# ODU_Display_0603.net
KiCad netlist of a schematic drawn in EAGLE
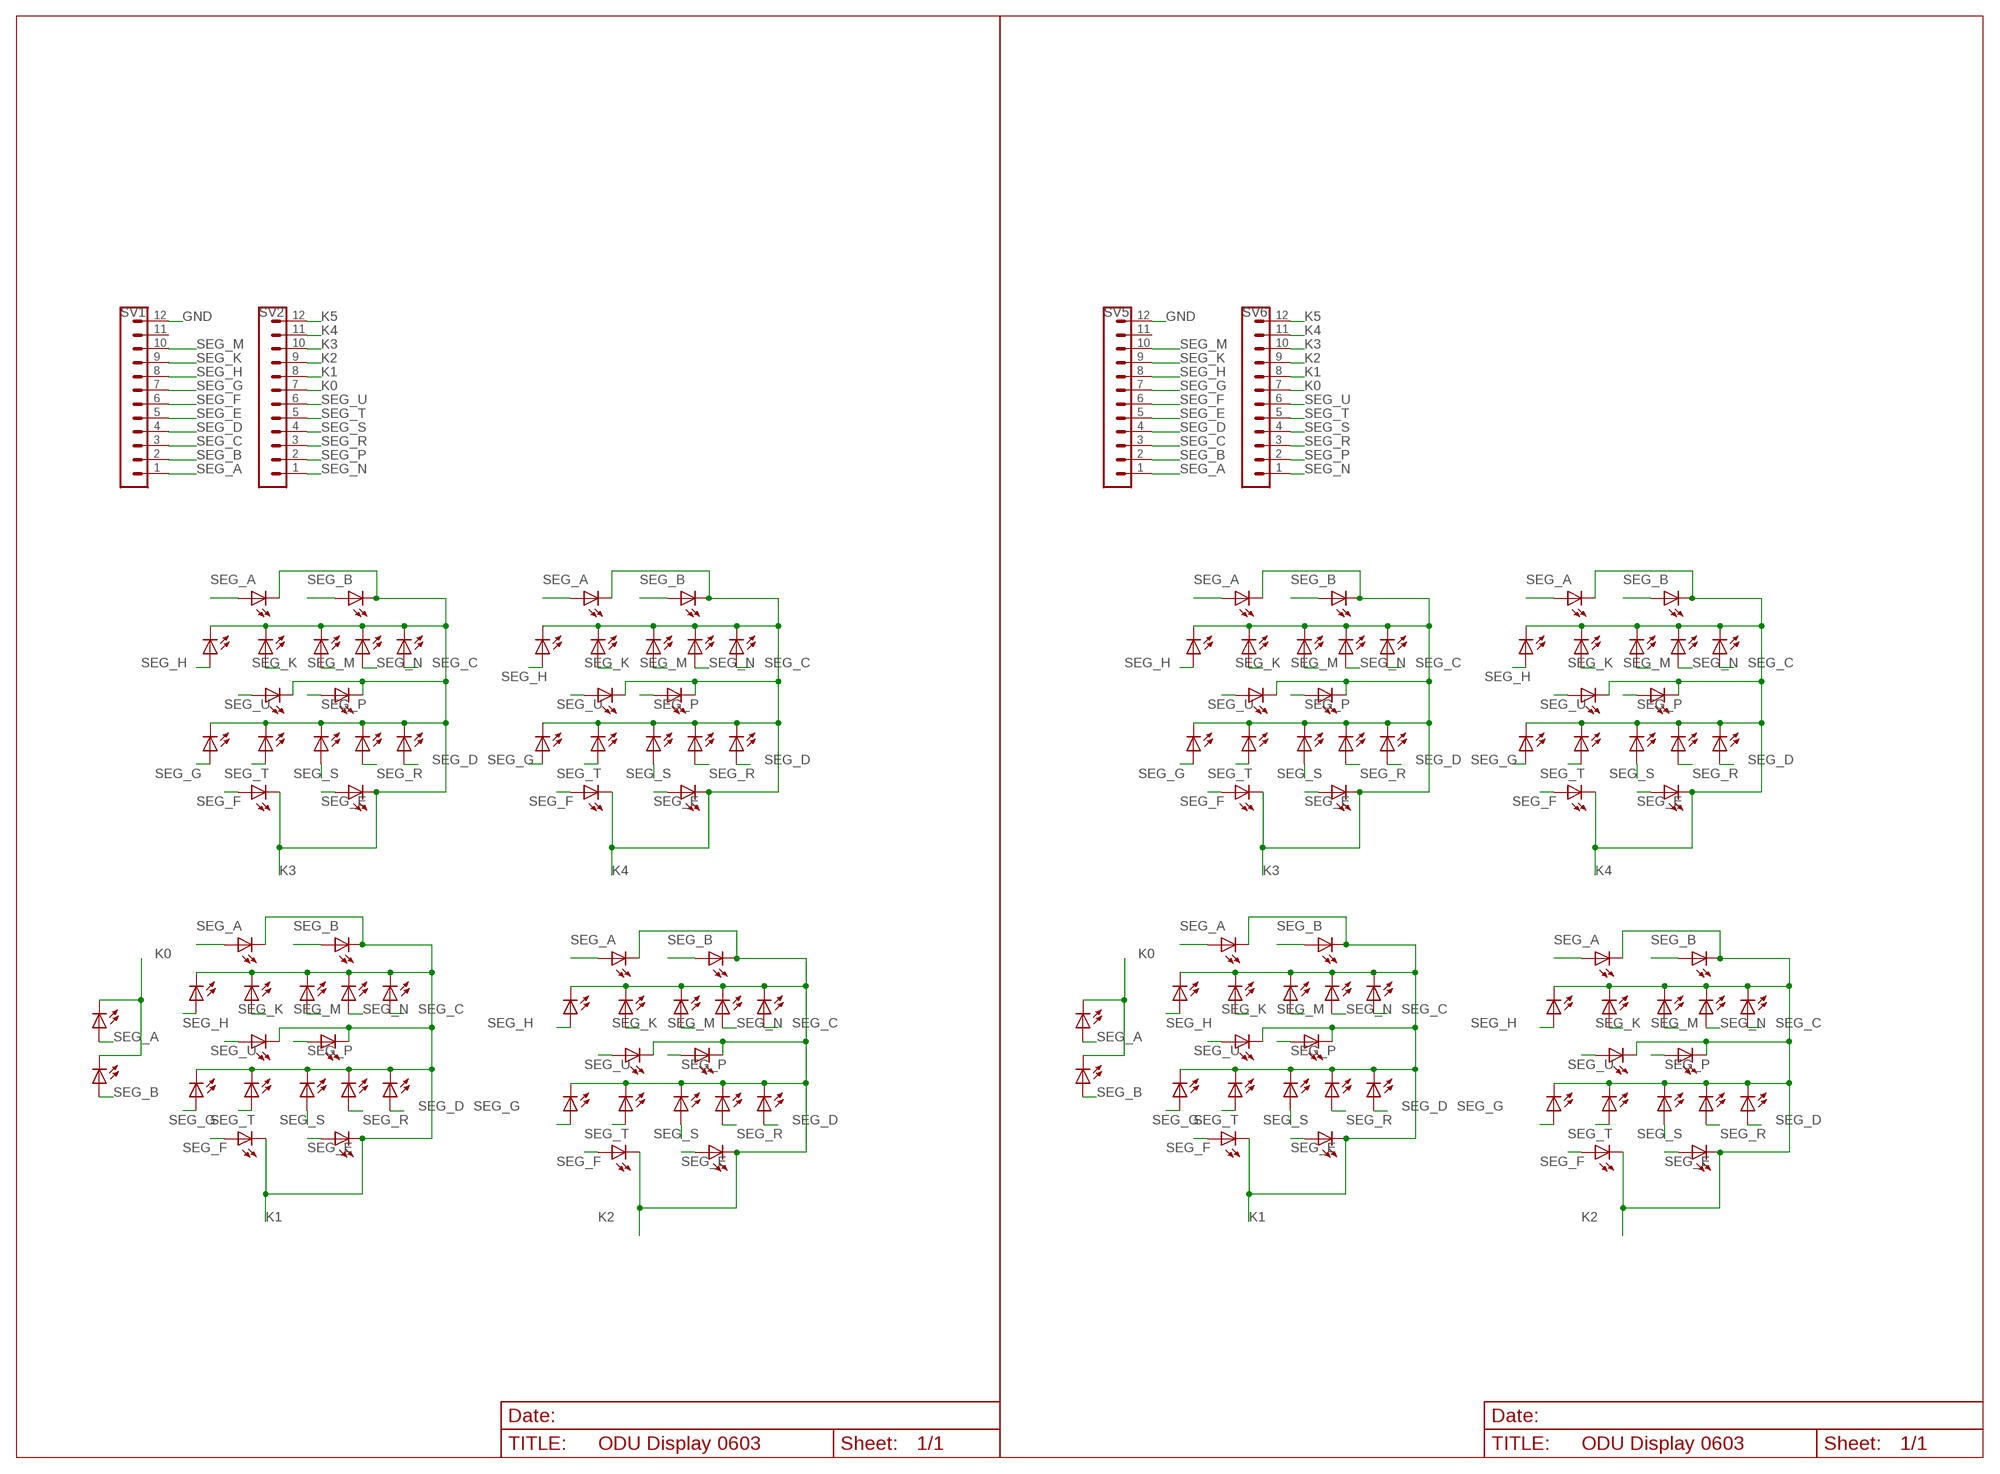
[diagram p0: schematic, sheet 1]

(export (version "E")
  (design (tool "Eeschema 10.0.6"))
  (components
    (comp (ref "LED_A1")
      (value "LEDSMT0603_1")
      (footprint "eagle-import:CHIPLED_0603")
      (libsource (lib "eagle-import") (part "LED0603_1SMT"))
    )
    (comp (ref "LED_A2")
      (value "LEDSMT0603_1")
      (footprint "eagle-import:CHIPLED_0603")
      (libsource (lib "eagle-import") (part "LED0603_1SMT"))
    )
    (comp (ref "LED_A3")
      (value "LEDSMT0603_1")
      (footprint "eagle-import:CHIPLED_0603")
      (libsource (lib "eagle-import") (part "LED0603_1SMT"))
    )
    (comp (ref "LED_A4")
      (value "LEDSMT0603_1")
      (footprint "eagle-import:CHIPLED_0603")
      (libsource (lib "eagle-import") (part "LED0603_1SMT"))
    )
    (comp (ref "LED_A9")
      (value "LEDSMT0603_1")
      (footprint "eagle-import:CHIPLED_0603")
      (libsource (lib "eagle-import") (part "LED0603_1SMT"))
    )
    (comp (ref "LED_A10")
      (value "LEDSMT0603_1")
      (footprint "eagle-import:CHIPLED_0603")
      (libsource (lib "eagle-import") (part "LED0603_1SMT"))
    )
    (comp (ref "LED_A11")
      (value "LEDSMT0603_1")
      (footprint "eagle-import:CHIPLED_0603")
      (libsource (lib "eagle-import") (part "LED0603_1SMT"))
    )
    (comp (ref "LED_A12")
      (value "LEDSMT0603_1")
      (footprint "eagle-import:CHIPLED_0603")
      (libsource (lib "eagle-import") (part "LED0603_1SMT"))
    )
    (comp (ref "LED_B1")
      (value "LEDSMT0603_1")
      (footprint "eagle-import:CHIPLED_0603")
      (libsource (lib "eagle-import") (part "LED0603_1SMT"))
    )
    (comp (ref "LED_B2")
      (value "LEDSMT0603_1")
      (footprint "eagle-import:CHIPLED_0603")
      (libsource (lib "eagle-import") (part "LED0603_1SMT"))
    )
    (comp (ref "LED_B3")
      (value "LEDSMT0603_1")
      (footprint "eagle-import:CHIPLED_0603")
      (libsource (lib "eagle-import") (part "LED0603_1SMT"))
    )
    (comp (ref "LED_B4")
      (value "LEDSMT0603_1")
      (footprint "eagle-import:CHIPLED_0603")
      (libsource (lib "eagle-import") (part "LED0603_1SMT"))
    )
    (comp (ref "LED_B9")
      (value "LEDSMT0603_1")
      (footprint "eagle-import:CHIPLED_0603")
      (libsource (lib "eagle-import") (part "LED0603_1SMT"))
    )
    (comp (ref "LED_B10")
      (value "LEDSMT0603_1")
      (footprint "eagle-import:CHIPLED_0603")
      (libsource (lib "eagle-import") (part "LED0603_1SMT"))
    )
    (comp (ref "LED_B11")
      (value "LEDSMT0603_1")
      (footprint "eagle-import:CHIPLED_0603")
      (libsource (lib "eagle-import") (part "LED0603_1SMT"))
    )
    (comp (ref "LED_B12")
      (value "LEDSMT0603_1")
      (footprint "eagle-import:CHIPLED_0603")
      (libsource (lib "eagle-import") (part "LED0603_1SMT"))
    )
    (comp (ref "LED_C1")
      (value "LEDSMT0603_1")
      (footprint "eagle-import:CHIPLED_0603")
      (libsource (lib "eagle-import") (part "LED0603_1SMT"))
    )
    (comp (ref "LED_C2")
      (value "LEDSMT0603_1")
      (footprint "eagle-import:CHIPLED_0603")
      (libsource (lib "eagle-import") (part "LED0603_1SMT"))
    )
    (comp (ref "LED_C3")
      (value "LEDSMT0603_1")
      (footprint "eagle-import:CHIPLED_0603")
      (libsource (lib "eagle-import") (part "LED0603_1SMT"))
    )
    (comp (ref "LED_C4")
      (value "LEDSMT0603_1")
      (footprint "eagle-import:CHIPLED_0603")
      (libsource (lib "eagle-import") (part "LED0603_1SMT"))
    )
    (comp (ref "LED_C9")
      (value "LEDSMT0603_1")
      (footprint "eagle-import:CHIPLED_0603")
      (libsource (lib "eagle-import") (part "LED0603_1SMT"))
    )
    (comp (ref "LED_C10")
      (value "LEDSMT0603_1")
      (footprint "eagle-import:CHIPLED_0603")
      (libsource (lib "eagle-import") (part "LED0603_1SMT"))
    )
    (comp (ref "LED_C11")
      (value "LEDSMT0603_1")
      (footprint "eagle-import:CHIPLED_0603")
      (libsource (lib "eagle-import") (part "LED0603_1SMT"))
    )
    (comp (ref "LED_C12")
      (value "LEDSMT0603_1")
      (footprint "eagle-import:CHIPLED_0603")
      (libsource (lib "eagle-import") (part "LED0603_1SMT"))
    )
    (comp (ref "LED_D1")
      (value "LEDSMT0603_1")
      (footprint "eagle-import:CHIPLED_0603")
      (libsource (lib "eagle-import") (part "LED0603_1SMT"))
    )
    (comp (ref "LED_D2")
      (value "LEDSMT0603_1")
      (footprint "eagle-import:CHIPLED_0603")
      (libsource (lib "eagle-import") (part "LED0603_1SMT"))
    )
    (comp (ref "LED_D3")
      (value "LEDSMT0603_1")
      (footprint "eagle-import:CHIPLED_0603")
      (libsource (lib "eagle-import") (part "LED0603_1SMT"))
    )
    (comp (ref "LED_D4")
      (value "LEDSMT0603_1")
      (footprint "eagle-import:CHIPLED_0603")
      (libsource (lib "eagle-import") (part "LED0603_1SMT"))
    )
    (comp (ref "LED_D9")
      (value "LEDSMT0603_1")
      (footprint "eagle-import:CHIPLED_0603")
      (libsource (lib "eagle-import") (part "LED0603_1SMT"))
    )
    (comp (ref "LED_D10")
      (value "LEDSMT0603_1")
      (footprint "eagle-import:CHIPLED_0603")
      (libsource (lib "eagle-import") (part "LED0603_1SMT"))
    )
    (comp (ref "LED_D11")
      (value "LEDSMT0603_1")
      (footprint "eagle-import:CHIPLED_0603")
      (libsource (lib "eagle-import") (part "LED0603_1SMT"))
    )
    (comp (ref "LED_D12")
      (value "LEDSMT0603_1")
      (footprint "eagle-import:CHIPLED_0603")
      (libsource (lib "eagle-import") (part "LED0603_1SMT"))
    )
    (comp (ref "LED_E1")
      (value "LEDSMT0603_1")
      (footprint "eagle-import:CHIPLED_0603")
      (libsource (lib "eagle-import") (part "LED0603_1SMT"))
    )
    (comp (ref "LED_E2")
      (value "LEDSMT0603_1")
      (footprint "eagle-import:CHIPLED_0603")
      (libsource (lib "eagle-import") (part "LED0603_1SMT"))
    )
    (comp (ref "LED_E3")
      (value "LEDSMT0603_1")
      (footprint "eagle-import:CHIPLED_0603")
      (libsource (lib "eagle-import") (part "LED0603_1SMT"))
    )
    (comp (ref "LED_E4")
      (value "LEDSMT0603_1")
      (footprint "eagle-import:CHIPLED_0603")
      (libsource (lib "eagle-import") (part "LED0603_1SMT"))
    )
    (comp (ref "LED_E9")
      (value "LEDSMT0603_1")
      (footprint "eagle-import:CHIPLED_0603")
      (libsource (lib "eagle-import") (part "LED0603_1SMT"))
    )
    (comp (ref "LED_E10")
      (value "LEDSMT0603_1")
      (footprint "eagle-import:CHIPLED_0603")
      (libsource (lib "eagle-import") (part "LED0603_1SMT"))
    )
    (comp (ref "LED_E11")
      (value "LEDSMT0603_1")
      (footprint "eagle-import:CHIPLED_0603")
      (libsource (lib "eagle-import") (part "LED0603_1SMT"))
    )
    (comp (ref "LED_E12")
      (value "LEDSMT0603_1")
      (footprint "eagle-import:CHIPLED_0603")
      (libsource (lib "eagle-import") (part "LED0603_1SMT"))
    )
    (comp (ref "LED_F1")
      (value "LEDSMT0603_1")
      (footprint "eagle-import:CHIPLED_0603")
      (libsource (lib "eagle-import") (part "LED0603_1SMT"))
    )
    (comp (ref "LED_F2")
      (value "LEDSMT0603_1")
      (footprint "eagle-import:CHIPLED_0603")
      (libsource (lib "eagle-import") (part "LED0603_1SMT"))
    )
    (comp (ref "LED_F3")
      (value "LEDSMT0603_1")
      (footprint "eagle-import:CHIPLED_0603")
      (libsource (lib "eagle-import") (part "LED0603_1SMT"))
    )
    (comp (ref "LED_F4")
      (value "LEDSMT0603_1")
      (footprint "eagle-import:CHIPLED_0603")
      (libsource (lib "eagle-import") (part "LED0603_1SMT"))
    )
    (comp (ref "LED_F9")
      (value "LEDSMT0603_1")
      (footprint "eagle-import:CHIPLED_0603")
      (libsource (lib "eagle-import") (part "LED0603_1SMT"))
    )
    (comp (ref "LED_F10")
      (value "LEDSMT0603_1")
      (footprint "eagle-import:CHIPLED_0603")
      (libsource (lib "eagle-import") (part "LED0603_1SMT"))
    )
    (comp (ref "LED_F11")
      (value "LEDSMT0603_1")
      (footprint "eagle-import:CHIPLED_0603")
      (libsource (lib "eagle-import") (part "LED0603_1SMT"))
    )
    (comp (ref "LED_F12")
      (value "LEDSMT0603_1")
      (footprint "eagle-import:CHIPLED_0603")
      (libsource (lib "eagle-import") (part "LED0603_1SMT"))
    )
    (comp (ref "LED_G1")
      (value "LEDSMT0603_1")
      (footprint "eagle-import:CHIPLED_0603")
      (libsource (lib "eagle-import") (part "LED0603_1SMT"))
    )
    (comp (ref "LED_G2")
      (value "LEDSMT0603_1")
      (footprint "eagle-import:CHIPLED_0603")
      (libsource (lib "eagle-import") (part "LED0603_1SMT"))
    )
    (comp (ref "LED_G3")
      (value "LEDSMT0603_1")
      (footprint "eagle-import:CHIPLED_0603")
      (libsource (lib "eagle-import") (part "LED0603_1SMT"))
    )
    (comp (ref "LED_G4")
      (value "LEDSMT0603_1")
      (footprint "eagle-import:CHIPLED_0603")
      (libsource (lib "eagle-import") (part "LED0603_1SMT"))
    )
    (comp (ref "LED_G9")
      (value "LEDSMT0603_1")
      (footprint "eagle-import:CHIPLED_0603")
      (libsource (lib "eagle-import") (part "LED0603_1SMT"))
    )
    (comp (ref "LED_G10")
      (value "LEDSMT0603_1")
      (footprint "eagle-import:CHIPLED_0603")
      (libsource (lib "eagle-import") (part "LED0603_1SMT"))
    )
    (comp (ref "LED_G11")
      (value "LEDSMT0603_1")
      (footprint "eagle-import:CHIPLED_0603")
      (libsource (lib "eagle-import") (part "LED0603_1SMT"))
    )
    (comp (ref "LED_G12")
      (value "LEDSMT0603_1")
      (footprint "eagle-import:CHIPLED_0603")
      (libsource (lib "eagle-import") (part "LED0603_1SMT"))
    )
    (comp (ref "LED_H1")
      (value "LEDSMT0603_1")
      (footprint "eagle-import:CHIPLED_0603")
      (libsource (lib "eagle-import") (part "LED0603_1SMT"))
    )
    (comp (ref "LED_H2")
      (value "LEDSMT0603_1")
      (footprint "eagle-import:CHIPLED_0603")
      (libsource (lib "eagle-import") (part "LED0603_1SMT"))
    )
    (comp (ref "LED_H3")
      (value "LEDSMT0603_1")
      (footprint "eagle-import:CHIPLED_0603")
      (libsource (lib "eagle-import") (part "LED0603_1SMT"))
    )
    (comp (ref "LED_H4")
      (value "LEDSMT0603_1")
      (footprint "eagle-import:CHIPLED_0603")
      (libsource (lib "eagle-import") (part "LED0603_1SMT"))
    )
    (comp (ref "LED_H9")
      (value "LEDSMT0603_1")
      (footprint "eagle-import:CHIPLED_0603")
      (libsource (lib "eagle-import") (part "LED0603_1SMT"))
    )
    (comp (ref "LED_H10")
      (value "LEDSMT0603_1")
      (footprint "eagle-import:CHIPLED_0603")
      (libsource (lib "eagle-import") (part "LED0603_1SMT"))
    )
    (comp (ref "LED_H11")
      (value "LEDSMT0603_1")
      (footprint "eagle-import:CHIPLED_0603")
      (libsource (lib "eagle-import") (part "LED0603_1SMT"))
    )
    (comp (ref "LED_H12")
      (value "LEDSMT0603_1")
      (footprint "eagle-import:CHIPLED_0603")
      (libsource (lib "eagle-import") (part "LED0603_1SMT"))
    )
    (comp (ref "LED_K1")
      (value "LEDSMT0603_1")
      (footprint "eagle-import:CHIPLED_0603")
      (libsource (lib "eagle-import") (part "LED0603_1SMT"))
    )
    (comp (ref "LED_K2")
      (value "LEDSMT0603_1")
      (footprint "eagle-import:CHIPLED_0603")
      (libsource (lib "eagle-import") (part "LED0603_1SMT"))
    )
    (comp (ref "LED_K3")
      (value "LEDSMT0603_1")
      (footprint "eagle-import:CHIPLED_0603")
      (libsource (lib "eagle-import") (part "LED0603_1SMT"))
    )
    (comp (ref "LED_K4")
      (value "LEDSMT0603_1")
      (footprint "eagle-import:CHIPLED_0603")
      (libsource (lib "eagle-import") (part "LED0603_1SMT"))
    )
    (comp (ref "LED_K9")
      (value "LEDSMT0603_1")
      (footprint "eagle-import:CHIPLED_0603")
      (libsource (lib "eagle-import") (part "LED0603_1SMT"))
    )
    (comp (ref "LED_K10")
      (value "LEDSMT0603_1")
      (footprint "eagle-import:CHIPLED_0603")
      (libsource (lib "eagle-import") (part "LED0603_1SMT"))
    )
    (comp (ref "LED_K11")
      (value "LEDSMT0603_1")
      (footprint "eagle-import:CHIPLED_0603")
      (libsource (lib "eagle-import") (part "LED0603_1SMT"))
    )
    (comp (ref "LED_K12")
      (value "LEDSMT0603_1")
      (footprint "eagle-import:CHIPLED_0603")
      (libsource (lib "eagle-import") (part "LED0603_1SMT"))
    )
    (comp (ref "LED_M1")
      (value "LEDSMT0603_1")
      (footprint "eagle-import:CHIPLED_0603")
      (libsource (lib "eagle-import") (part "LED0603_1SMT"))
    )
    (comp (ref "LED_M2")
      (value "LEDSMT0603_1")
      (footprint "eagle-import:CHIPLED_0603")
      (libsource (lib "eagle-import") (part "LED0603_1SMT"))
    )
    (comp (ref "LED_M3")
      (value "LEDSMT0603_1")
      (footprint "eagle-import:CHIPLED_0603")
      (libsource (lib "eagle-import") (part "LED0603_1SMT"))
    )
    (comp (ref "LED_M4")
      (value "LEDSMT0603_1")
      (footprint "eagle-import:CHIPLED_0603")
      (libsource (lib "eagle-import") (part "LED0603_1SMT"))
    )
    (comp (ref "LED_M9")
      (value "LEDSMT0603_1")
      (footprint "eagle-import:CHIPLED_0603")
      (libsource (lib "eagle-import") (part "LED0603_1SMT"))
    )
    (comp (ref "LED_M10")
      (value "LEDSMT0603_1")
      (footprint "eagle-import:CHIPLED_0603")
      (libsource (lib "eagle-import") (part "LED0603_1SMT"))
    )
    (comp (ref "LED_M11")
      (value "LEDSMT0603_1")
      (footprint "eagle-import:CHIPLED_0603")
      (libsource (lib "eagle-import") (part "LED0603_1SMT"))
    )
    (comp (ref "LED_M12")
      (value "LEDSMT0603_1")
      (footprint "eagle-import:CHIPLED_0603")
      (libsource (lib "eagle-import") (part "LED0603_1SMT"))
    )
    (comp (ref "LED_N1")
      (value "LEDSMT0603_1")
      (footprint "eagle-import:CHIPLED_0603")
      (libsource (lib "eagle-import") (part "LED0603_1SMT"))
    )
    (comp (ref "LED_N2")
      (value "LEDSMT0603_1")
      (footprint "eagle-import:CHIPLED_0603")
      (libsource (lib "eagle-import") (part "LED0603_1SMT"))
    )
    (comp (ref "LED_N3")
      (value "LEDSMT0603_1")
      (footprint "eagle-import:CHIPLED_0603")
      (libsource (lib "eagle-import") (part "LED0603_1SMT"))
    )
    (comp (ref "LED_N4")
      (value "LEDSMT0603_1")
      (footprint "eagle-import:CHIPLED_0603")
      (libsource (lib "eagle-import") (part "LED0603_1SMT"))
    )
    (comp (ref "LED_N9")
      (value "LEDSMT0603_1")
      (footprint "eagle-import:CHIPLED_0603")
      (libsource (lib "eagle-import") (part "LED0603_1SMT"))
    )
    (comp (ref "LED_N10")
      (value "LEDSMT0603_1")
      (footprint "eagle-import:CHIPLED_0603")
      (libsource (lib "eagle-import") (part "LED0603_1SMT"))
    )
    (comp (ref "LED_N11")
      (value "LEDSMT0603_1")
      (footprint "eagle-import:CHIPLED_0603")
      (libsource (lib "eagle-import") (part "LED0603_1SMT"))
    )
    (comp (ref "LED_N12")
      (value "LEDSMT0603_1")
      (footprint "eagle-import:CHIPLED_0603")
      (libsource (lib "eagle-import") (part "LED0603_1SMT"))
    )
    (comp (ref "LED_P1")
      (value "LEDSMT0603_1")
      (footprint "eagle-import:CHIPLED_0603")
      (libsource (lib "eagle-import") (part "LED0603_1SMT"))
    )
    (comp (ref "LED_P2")
      (value "LEDSMT0603_1")
      (footprint "eagle-import:CHIPLED_0603")
      (libsource (lib "eagle-import") (part "LED0603_1SMT"))
    )
    (comp (ref "LED_P3")
      (value "LEDSMT0603_1")
      (footprint "eagle-import:CHIPLED_0603")
      (libsource (lib "eagle-import") (part "LED0603_1SMT"))
    )
    (comp (ref "LED_P4")
      (value "LEDSMT0603_1")
      (footprint "eagle-import:CHIPLED_0603")
      (libsource (lib "eagle-import") (part "LED0603_1SMT"))
    )
    (comp (ref "LED_P9")
      (value "LEDSMT0603_1")
      (footprint "eagle-import:CHIPLED_0603")
      (libsource (lib "eagle-import") (part "LED0603_1SMT"))
    )
    (comp (ref "LED_P10")
      (value "LEDSMT0603_1")
      (footprint "eagle-import:CHIPLED_0603")
      (libsource (lib "eagle-import") (part "LED0603_1SMT"))
    )
    (comp (ref "LED_P11")
      (value "LEDSMT0603_1")
      (footprint "eagle-import:CHIPLED_0603")
      (libsource (lib "eagle-import") (part "LED0603_1SMT"))
    )
    (comp (ref "LED_P12")
      (value "LEDSMT0603_1")
      (footprint "eagle-import:CHIPLED_0603")
      (libsource (lib "eagle-import") (part "LED0603_1SMT"))
    )
    (comp (ref "LED_R1")
      (value "LEDSMT0603_1")
      (footprint "eagle-import:CHIPLED_0603")
      (libsource (lib "eagle-import") (part "LED0603_1SMT"))
    )
    (comp (ref "LED_R2")
      (value "LEDSMT0603_1")
      (footprint "eagle-import:CHIPLED_0603")
      (libsource (lib "eagle-import") (part "LED0603_1SMT"))
    )
    (comp (ref "LED_R3")
      (value "LEDSMT0603_1")
      (footprint "eagle-import:CHIPLED_0603")
      (libsource (lib "eagle-import") (part "LED0603_1SMT"))
    )
    (comp (ref "LED_R4")
      (value "LEDSMT0603_1")
      (footprint "eagle-import:CHIPLED_0603")
      (libsource (lib "eagle-import") (part "LED0603_1SMT"))
    )
    (comp (ref "LED_R9")
      (value "LEDSMT0603_1")
      (footprint "eagle-import:CHIPLED_0603")
      (libsource (lib "eagle-import") (part "LED0603_1SMT"))
    )
    (comp (ref "LED_R10")
      (value "LEDSMT0603_1")
      (footprint "eagle-import:CHIPLED_0603")
      (libsource (lib "eagle-import") (part "LED0603_1SMT"))
    )
    (comp (ref "LED_R11")
      (value "LEDSMT0603_1")
      (footprint "eagle-import:CHIPLED_0603")
      (libsource (lib "eagle-import") (part "LED0603_1SMT"))
    )
    (comp (ref "LED_R12")
      (value "LEDSMT0603_1")
      (footprint "eagle-import:CHIPLED_0603")
      (libsource (lib "eagle-import") (part "LED0603_1SMT"))
    )
    (comp (ref "LED_S1")
      (value "LEDSMT0603_1")
      (footprint "eagle-import:CHIPLED_0603")
      (libsource (lib "eagle-import") (part "LED0603_1SMT"))
    )
    (comp (ref "LED_S2")
      (value "LEDSMT0603_1")
      (footprint "eagle-import:CHIPLED_0603")
      (libsource (lib "eagle-import") (part "LED0603_1SMT"))
    )
    (comp (ref "LED_S3")
      (value "LEDSMT0603_1")
      (footprint "eagle-import:CHIPLED_0603")
      (libsource (lib "eagle-import") (part "LED0603_1SMT"))
    )
    (comp (ref "LED_S4")
      (value "LEDSMT0603_1")
      (footprint "eagle-import:CHIPLED_0603")
      (libsource (lib "eagle-import") (part "LED0603_1SMT"))
    )
    (comp (ref "LED_S9")
      (value "LEDSMT0603_1")
      (footprint "eagle-import:CHIPLED_0603")
      (libsource (lib "eagle-import") (part "LED0603_1SMT"))
    )
    (comp (ref "LED_S10")
      (value "LEDSMT0603_1")
      (footprint "eagle-import:CHIPLED_0603")
      (libsource (lib "eagle-import") (part "LED0603_1SMT"))
    )
    (comp (ref "LED_S11")
      (value "LEDSMT0603_1")
      (footprint "eagle-import:CHIPLED_0603")
      (libsource (lib "eagle-import") (part "LED0603_1SMT"))
    )
    (comp (ref "LED_S12")
      (value "LEDSMT0603_1")
      (footprint "eagle-import:CHIPLED_0603")
      (libsource (lib "eagle-import") (part "LED0603_1SMT"))
    )
    (comp (ref "LED_SEL1")
      (value "LEDSMT0603_1")
      (footprint "eagle-import:CHIPLED_0603")
      (libsource (lib "eagle-import") (part "LED0603_1SMT"))
    )
    (comp (ref "LED_SEL2")
      (value "LEDSMT0603_1")
      (footprint "eagle-import:CHIPLED_0603")
      (libsource (lib "eagle-import") (part "LED0603_1SMT"))
    )
    (comp (ref "LED_SEL5")
      (value "LEDSMT0603_1")
      (footprint "eagle-import:CHIPLED_0603")
      (libsource (lib "eagle-import") (part "LED0603_1SMT"))
    )
    (comp (ref "LED_SEL6")
      (value "LEDSMT0603_1")
      (footprint "eagle-import:CHIPLED_0603")
      (libsource (lib "eagle-import") (part "LED0603_1SMT"))
    )
    (comp (ref "LED_T1")
      (value "LEDSMT0603_1")
      (footprint "eagle-import:CHIPLED_0603")
      (libsource (lib "eagle-import") (part "LED0603_1SMT"))
    )
    (comp (ref "LED_T2")
      (value "LEDSMT0603_1")
      (footprint "eagle-import:CHIPLED_0603")
      (libsource (lib "eagle-import") (part "LED0603_1SMT"))
    )
    (comp (ref "LED_T3")
      (value "LEDSMT0603_1")
      (footprint "eagle-import:CHIPLED_0603")
      (libsource (lib "eagle-import") (part "LED0603_1SMT"))
    )
    (comp (ref "LED_T4")
      (value "LEDSMT0603_1")
      (footprint "eagle-import:CHIPLED_0603")
      (libsource (lib "eagle-import") (part "LED0603_1SMT"))
    )
    (comp (ref "LED_T9")
      (value "LEDSMT0603_1")
      (footprint "eagle-import:CHIPLED_0603")
      (libsource (lib "eagle-import") (part "LED0603_1SMT"))
    )
    (comp (ref "LED_T10")
      (value "LEDSMT0603_1")
      (footprint "eagle-import:CHIPLED_0603")
      (libsource (lib "eagle-import") (part "LED0603_1SMT"))
    )
    (comp (ref "LED_T11")
      (value "LEDSMT0603_1")
      (footprint "eagle-import:CHIPLED_0603")
      (libsource (lib "eagle-import") (part "LED0603_1SMT"))
    )
    (comp (ref "LED_T12")
      (value "LEDSMT0603_1")
      (footprint "eagle-import:CHIPLED_0603")
      (libsource (lib "eagle-import") (part "LED0603_1SMT"))
    )
    (comp (ref "LED_U1")
      (value "LEDSMT0603_1")
      (footprint "eagle-import:CHIPLED_0603")
      (libsource (lib "eagle-import") (part "LED0603_1SMT"))
    )
    (comp (ref "LED_U2")
      (value "LEDSMT0603_1")
      (footprint "eagle-import:CHIPLED_0603")
      (libsource (lib "eagle-import") (part "LED0603_1SMT"))
    )
    (comp (ref "LED_U3")
      (value "LEDSMT0603_1")
      (footprint "eagle-import:CHIPLED_0603")
      (libsource (lib "eagle-import") (part "LED0603_1SMT"))
    )
    (comp (ref "LED_U4")
      (value "LEDSMT0603_1")
      (footprint "eagle-import:CHIPLED_0603")
      (libsource (lib "eagle-import") (part "LED0603_1SMT"))
    )
    (comp (ref "LED_U9")
      (value "LEDSMT0603_1")
      (footprint "eagle-import:CHIPLED_0603")
      (libsource (lib "eagle-import") (part "LED0603_1SMT"))
    )
    (comp (ref "LED_U10")
      (value "LEDSMT0603_1")
      (footprint "eagle-import:CHIPLED_0603")
      (libsource (lib "eagle-import") (part "LED0603_1SMT"))
    )
    (comp (ref "LED_U11")
      (value "LEDSMT0603_1")
      (footprint "eagle-import:CHIPLED_0603")
      (libsource (lib "eagle-import") (part "LED0603_1SMT"))
    )
    (comp (ref "LED_U12")
      (value "LEDSMT0603_1")
      (footprint "eagle-import:CHIPLED_0603")
      (libsource (lib "eagle-import") (part "LED0603_1SMT"))
    )
    (comp (ref "SV1")
      (value "MA12-1")
      (footprint "eagle-import:MA12-1")
      (libsource (lib "eagle-import") (part "MA12-1"))
    )
    (comp (ref "SV2")
      (value "MA12-1")
      (footprint "eagle-import:MA12-1")
      (libsource (lib "eagle-import") (part "MA12-1"))
    )
    (comp (ref "SV5")
      (value "MA12-1")
      (footprint "eagle-import:MA12-1")
      (libsource (lib "eagle-import") (part "MA12-1"))
    )
    (comp (ref "SV6")
      (value "MA12-1")
      (footprint "eagle-import:MA12-1")
      (libsource (lib "eagle-import") (part "MA12-1"))
    )
  )
  (nets
    (net (code "1") (name "/GND") (class "Default")
      (node (ref "SV1") (pin "12") (pinfunction "12_12") (pintype "passive"))
      (node (ref "SV5") (pin "12") (pinfunction "12_12") (pintype "passive"))
    )
    (net (code "2") (name "/K0") (class "Default")
      (node (ref "LED_SEL1") (pin "C") (pinfunction "C_C") (pintype "passive"))
      (node (ref "LED_SEL2") (pin "C") (pinfunction "C_C") (pintype "passive"))
      (node (ref "LED_SEL5") (pin "C") (pinfunction "C_C") (pintype "passive"))
      (node (ref "LED_SEL6") (pin "C") (pinfunction "C_C") (pintype "passive"))
      (node (ref "SV2") (pin "7") (pinfunction "7_7") (pintype "passive"))
      (node (ref "SV6") (pin "7") (pinfunction "7_7") (pintype "passive"))
    )
    (net (code "3") (name "/K1") (class "Default")
      (node (ref "LED_A1") (pin "C") (pinfunction "C_C") (pintype "passive"))
      (node (ref "LED_A9") (pin "C") (pinfunction "C_C") (pintype "passive"))
      (node (ref "LED_B1") (pin "C") (pinfunction "C_C") (pintype "passive"))
      (node (ref "LED_B9") (pin "C") (pinfunction "C_C") (pintype "passive"))
      (node (ref "LED_C1") (pin "C") (pinfunction "C_C") (pintype "passive"))
      (node (ref "LED_C9") (pin "C") (pinfunction "C_C") (pintype "passive"))
      (node (ref "LED_D1") (pin "C") (pinfunction "C_C") (pintype "passive"))
      (node (ref "LED_D9") (pin "C") (pinfunction "C_C") (pintype "passive"))
      (node (ref "LED_E1") (pin "C") (pinfunction "C_C") (pintype "passive"))
      (node (ref "LED_E9") (pin "C") (pinfunction "C_C") (pintype "passive"))
      (node (ref "LED_F1") (pin "C") (pinfunction "C_C") (pintype "passive"))
      (node (ref "LED_F9") (pin "C") (pinfunction "C_C") (pintype "passive"))
      (node (ref "LED_G1") (pin "C") (pinfunction "C_C") (pintype "passive"))
      (node (ref "LED_G9") (pin "C") (pinfunction "C_C") (pintype "passive"))
      (node (ref "LED_H1") (pin "C") (pinfunction "C_C") (pintype "passive"))
      (node (ref "LED_H9") (pin "C") (pinfunction "C_C") (pintype "passive"))
      (node (ref "LED_K1") (pin "C") (pinfunction "C_C") (pintype "passive"))
      (node (ref "LED_K9") (pin "C") (pinfunction "C_C") (pintype "passive"))
      (node (ref "LED_M1") (pin "C") (pinfunction "C_C") (pintype "passive"))
      (node (ref "LED_M9") (pin "C") (pinfunction "C_C") (pintype "passive"))
      (node (ref "LED_N1") (pin "C") (pinfunction "C_C") (pintype "passive"))
      (node (ref "LED_N9") (pin "C") (pinfunction "C_C") (pintype "passive"))
      (node (ref "LED_P1") (pin "C") (pinfunction "C_C") (pintype "passive"))
      (node (ref "LED_P9") (pin "C") (pinfunction "C_C") (pintype "passive"))
      (node (ref "LED_R1") (pin "C") (pinfunction "C_C") (pintype "passive"))
      (node (ref "LED_R9") (pin "C") (pinfunction "C_C") (pintype "passive"))
      (node (ref "LED_S1") (pin "C") (pinfunction "C_C") (pintype "passive"))
      (node (ref "LED_S9") (pin "C") (pinfunction "C_C") (pintype "passive"))
      (node (ref "LED_T1") (pin "C") (pinfunction "C_C") (pintype "passive"))
      (node (ref "LED_T9") (pin "C") (pinfunction "C_C") (pintype "passive"))
      (node (ref "LED_U1") (pin "C") (pinfunction "C_C") (pintype "passive"))
      (node (ref "LED_U9") (pin "C") (pinfunction "C_C") (pintype "passive"))
      (node (ref "SV2") (pin "8") (pinfunction "8_8") (pintype "passive"))
      (node (ref "SV6") (pin "8") (pinfunction "8_8") (pintype "passive"))
    )
    (net (code "4") (name "/K2") (class "Default")
      (node (ref "LED_A10") (pin "C") (pinfunction "C_C") (pintype "passive"))
      (node (ref "LED_A2") (pin "C") (pinfunction "C_C") (pintype "passive"))
      (node (ref "LED_B10") (pin "C") (pinfunction "C_C") (pintype "passive"))
      (node (ref "LED_B2") (pin "C") (pinfunction "C_C") (pintype "passive"))
      (node (ref "LED_C10") (pin "C") (pinfunction "C_C") (pintype "passive"))
      (node (ref "LED_C2") (pin "C") (pinfunction "C_C") (pintype "passive"))
      (node (ref "LED_D10") (pin "C") (pinfunction "C_C") (pintype "passive"))
      (node (ref "LED_D2") (pin "C") (pinfunction "C_C") (pintype "passive"))
      (node (ref "LED_E10") (pin "C") (pinfunction "C_C") (pintype "passive"))
      (node (ref "LED_E2") (pin "C") (pinfunction "C_C") (pintype "passive"))
      (node (ref "LED_F10") (pin "C") (pinfunction "C_C") (pintype "passive"))
      (node (ref "LED_F2") (pin "C") (pinfunction "C_C") (pintype "passive"))
      (node (ref "LED_G10") (pin "C") (pinfunction "C_C") (pintype "passive"))
      (node (ref "LED_G2") (pin "C") (pinfunction "C_C") (pintype "passive"))
      (node (ref "LED_H10") (pin "C") (pinfunction "C_C") (pintype "passive"))
      (node (ref "LED_H2") (pin "C") (pinfunction "C_C") (pintype "passive"))
      (node (ref "LED_K10") (pin "C") (pinfunction "C_C") (pintype "passive"))
      (node (ref "LED_K2") (pin "C") (pinfunction "C_C") (pintype "passive"))
      (node (ref "LED_M10") (pin "C") (pinfunction "C_C") (pintype "passive"))
      (node (ref "LED_M2") (pin "C") (pinfunction "C_C") (pintype "passive"))
      (node (ref "LED_N10") (pin "C") (pinfunction "C_C") (pintype "passive"))
      (node (ref "LED_N2") (pin "C") (pinfunction "C_C") (pintype "passive"))
      (node (ref "LED_P10") (pin "C") (pinfunction "C_C") (pintype "passive"))
      (node (ref "LED_P2") (pin "C") (pinfunction "C_C") (pintype "passive"))
      (node (ref "LED_R10") (pin "C") (pinfunction "C_C") (pintype "passive"))
      (node (ref "LED_R2") (pin "C") (pinfunction "C_C") (pintype "passive"))
      (node (ref "LED_S10") (pin "C") (pinfunction "C_C") (pintype "passive"))
      (node (ref "LED_S2") (pin "C") (pinfunction "C_C") (pintype "passive"))
      (node (ref "LED_T10") (pin "C") (pinfunction "C_C") (pintype "passive"))
      (node (ref "LED_T2") (pin "C") (pinfunction "C_C") (pintype "passive"))
      (node (ref "LED_U10") (pin "C") (pinfunction "C_C") (pintype "passive"))
      (node (ref "LED_U2") (pin "C") (pinfunction "C_C") (pintype "passive"))
      (node (ref "SV2") (pin "9") (pinfunction "9_9") (pintype "passive"))
      (node (ref "SV6") (pin "9") (pinfunction "9_9") (pintype "passive"))
    )
    (net (code "5") (name "/K3") (class "Default")
      (node (ref "LED_A11") (pin "C") (pinfunction "C_C") (pintype "passive"))
      (node (ref "LED_A3") (pin "C") (pinfunction "C_C") (pintype "passive"))
      (node (ref "LED_B11") (pin "C") (pinfunction "C_C") (pintype "passive"))
      (node (ref "LED_B3") (pin "C") (pinfunction "C_C") (pintype "passive"))
      (node (ref "LED_C11") (pin "C") (pinfunction "C_C") (pintype "passive"))
      (node (ref "LED_C3") (pin "C") (pinfunction "C_C") (pintype "passive"))
      (node (ref "LED_D11") (pin "C") (pinfunction "C_C") (pintype "passive"))
      (node (ref "LED_D3") (pin "C") (pinfunction "C_C") (pintype "passive"))
      (node (ref "LED_E11") (pin "C") (pinfunction "C_C") (pintype "passive"))
      (node (ref "LED_E3") (pin "C") (pinfunction "C_C") (pintype "passive"))
      (node (ref "LED_F11") (pin "C") (pinfunction "C_C") (pintype "passive"))
      (node (ref "LED_F3") (pin "C") (pinfunction "C_C") (pintype "passive"))
      (node (ref "LED_G11") (pin "C") (pinfunction "C_C") (pintype "passive"))
      (node (ref "LED_G3") (pin "C") (pinfunction "C_C") (pintype "passive"))
      (node (ref "LED_H11") (pin "C") (pinfunction "C_C") (pintype "passive"))
      (node (ref "LED_H3") (pin "C") (pinfunction "C_C") (pintype "passive"))
      (node (ref "LED_K11") (pin "C") (pinfunction "C_C") (pintype "passive"))
      (node (ref "LED_K3") (pin "C") (pinfunction "C_C") (pintype "passive"))
      (node (ref "LED_M11") (pin "C") (pinfunction "C_C") (pintype "passive"))
      (node (ref "LED_M3") (pin "C") (pinfunction "C_C") (pintype "passive"))
      (node (ref "LED_N11") (pin "C") (pinfunction "C_C") (pintype "passive"))
      (node (ref "LED_N3") (pin "C") (pinfunction "C_C") (pintype "passive"))
      (node (ref "LED_P11") (pin "C") (pinfunction "C_C") (pintype "passive"))
      (node (ref "LED_P3") (pin "C") (pinfunction "C_C") (pintype "passive"))
      (node (ref "LED_R11") (pin "C") (pinfunction "C_C") (pintype "passive"))
      (node (ref "LED_R3") (pin "C") (pinfunction "C_C") (pintype "passive"))
      (node (ref "LED_S11") (pin "C") (pinfunction "C_C") (pintype "passive"))
      (node (ref "LED_S3") (pin "C") (pinfunction "C_C") (pintype "passive"))
      (node (ref "LED_T11") (pin "C") (pinfunction "C_C") (pintype "passive"))
      (node (ref "LED_T3") (pin "C") (pinfunction "C_C") (pintype "passive"))
      (node (ref "LED_U11") (pin "C") (pinfunction "C_C") (pintype "passive"))
      (node (ref "LED_U3") (pin "C") (pinfunction "C_C") (pintype "passive"))
      (node (ref "SV2") (pin "10") (pinfunction "10_10") (pintype "passive"))
      (node (ref "SV6") (pin "10") (pinfunction "10_10") (pintype "passive"))
    )
    (net (code "6") (name "/K4") (class "Default")
      (node (ref "LED_A12") (pin "C") (pinfunction "C_C") (pintype "passive"))
      (node (ref "LED_A4") (pin "C") (pinfunction "C_C") (pintype "passive"))
      (node (ref "LED_B12") (pin "C") (pinfunction "C_C") (pintype "passive"))
      (node (ref "LED_B4") (pin "C") (pinfunction "C_C") (pintype "passive"))
      (node (ref "LED_C12") (pin "C") (pinfunction "C_C") (pintype "passive"))
      (node (ref "LED_C4") (pin "C") (pinfunction "C_C") (pintype "passive"))
      (node (ref "LED_D12") (pin "C") (pinfunction "C_C") (pintype "passive"))
      (node (ref "LED_D4") (pin "C") (pinfunction "C_C") (pintype "passive"))
      (node (ref "LED_E12") (pin "C") (pinfunction "C_C") (pintype "passive"))
      (node (ref "LED_E4") (pin "C") (pinfunction "C_C") (pintype "passive"))
      (node (ref "LED_F12") (pin "C") (pinfunction "C_C") (pintype "passive"))
      (node (ref "LED_F4") (pin "C") (pinfunction "C_C") (pintype "passive"))
      (node (ref "LED_G12") (pin "C") (pinfunction "C_C") (pintype "passive"))
      (node (ref "LED_G4") (pin "C") (pinfunction "C_C") (pintype "passive"))
      (node (ref "LED_H12") (pin "C") (pinfunction "C_C") (pintype "passive"))
      (node (ref "LED_H4") (pin "C") (pinfunction "C_C") (pintype "passive"))
      (node (ref "LED_K12") (pin "C") (pinfunction "C_C") (pintype "passive"))
      (node (ref "LED_K4") (pin "C") (pinfunction "C_C") (pintype "passive"))
      (node (ref "LED_M12") (pin "C") (pinfunction "C_C") (pintype "passive"))
      (node (ref "LED_M4") (pin "C") (pinfunction "C_C") (pintype "passive"))
      (node (ref "LED_N12") (pin "C") (pinfunction "C_C") (pintype "passive"))
      (node (ref "LED_N4") (pin "C") (pinfunction "C_C") (pintype "passive"))
      (node (ref "LED_P12") (pin "C") (pinfunction "C_C") (pintype "passive"))
      (node (ref "LED_P4") (pin "C") (pinfunction "C_C") (pintype "passive"))
      (node (ref "LED_R12") (pin "C") (pinfunction "C_C") (pintype "passive"))
      (node (ref "LED_R4") (pin "C") (pinfunction "C_C") (pintype "passive"))
      (node (ref "LED_S12") (pin "C") (pinfunction "C_C") (pintype "passive"))
      (node (ref "LED_S4") (pin "C") (pinfunction "C_C") (pintype "passive"))
      (node (ref "LED_T12") (pin "C") (pinfunction "C_C") (pintype "passive"))
      (node (ref "LED_T4") (pin "C") (pinfunction "C_C") (pintype "passive"))
      (node (ref "LED_U12") (pin "C") (pinfunction "C_C") (pintype "passive"))
      (node (ref "LED_U4") (pin "C") (pinfunction "C_C") (pintype "passive"))
      (node (ref "SV2") (pin "11") (pinfunction "11_11") (pintype "passive"))
      (node (ref "SV6") (pin "11") (pinfunction "11_11") (pintype "passive"))
    )
    (net (code "7") (name "/K5") (class "Default")
      (node (ref "SV2") (pin "12") (pinfunction "12_12") (pintype "passive"))
      (node (ref "SV6") (pin "12") (pinfunction "12_12") (pintype "passive"))
    )
    (net (code "8") (name "/SEG_A") (class "Default")
      (node (ref "LED_A1") (pin "A") (pinfunction "A_A") (pintype "passive"))
      (node (ref "LED_A10") (pin "A") (pinfunction "A_A") (pintype "passive"))
      (node (ref "LED_A11") (pin "A") (pinfunction "A_A") (pintype "passive"))
      (node (ref "LED_A12") (pin "A") (pinfunction "A_A") (pintype "passive"))
      (node (ref "LED_A2") (pin "A") (pinfunction "A_A") (pintype "passive"))
      (node (ref "LED_A3") (pin "A") (pinfunction "A_A") (pintype "passive"))
      (node (ref "LED_A4") (pin "A") (pinfunction "A_A") (pintype "passive"))
      (node (ref "LED_A9") (pin "A") (pinfunction "A_A") (pintype "passive"))
      (node (ref "LED_SEL1") (pin "A") (pinfunction "A_A") (pintype "passive"))
      (node (ref "LED_SEL5") (pin "A") (pinfunction "A_A") (pintype "passive"))
      (node (ref "SV1") (pin "1") (pinfunction "1_1") (pintype "passive"))
      (node (ref "SV5") (pin "1") (pinfunction "1_1") (pintype "passive"))
    )
    (net (code "9") (name "/SEG_B") (class "Default")
      (node (ref "LED_B1") (pin "A") (pinfunction "A_A") (pintype "passive"))
      (node (ref "LED_B10") (pin "A") (pinfunction "A_A") (pintype "passive"))
      (node (ref "LED_B11") (pin "A") (pinfunction "A_A") (pintype "passive"))
      (node (ref "LED_B12") (pin "A") (pinfunction "A_A") (pintype "passive"))
      (node (ref "LED_B2") (pin "A") (pinfunction "A_A") (pintype "passive"))
      (node (ref "LED_B3") (pin "A") (pinfunction "A_A") (pintype "passive"))
      (node (ref "LED_B4") (pin "A") (pinfunction "A_A") (pintype "passive"))
      (node (ref "LED_B9") (pin "A") (pinfunction "A_A") (pintype "passive"))
      (node (ref "LED_SEL2") (pin "A") (pinfunction "A_A") (pintype "passive"))
      (node (ref "LED_SEL6") (pin "A") (pinfunction "A_A") (pintype "passive"))
      (node (ref "SV1") (pin "2") (pinfunction "2_2") (pintype "passive"))
      (node (ref "SV5") (pin "2") (pinfunction "2_2") (pintype "passive"))
    )
    (net (code "10") (name "/SEG_C") (class "Default")
      (node (ref "LED_C1") (pin "A") (pinfunction "A_A") (pintype "passive"))
      (node (ref "LED_C10") (pin "A") (pinfunction "A_A") (pintype "passive"))
      (node (ref "LED_C11") (pin "A") (pinfunction "A_A") (pintype "passive"))
      (node (ref "LED_C12") (pin "A") (pinfunction "A_A") (pintype "passive"))
      (node (ref "LED_C2") (pin "A") (pinfunction "A_A") (pintype "passive"))
      (node (ref "LED_C3") (pin "A") (pinfunction "A_A") (pintype "passive"))
      (node (ref "LED_C4") (pin "A") (pinfunction "A_A") (pintype "passive"))
      (node (ref "LED_C9") (pin "A") (pinfunction "A_A") (pintype "passive"))
      (node (ref "SV1") (pin "3") (pinfunction "3_3") (pintype "passive"))
      (node (ref "SV5") (pin "3") (pinfunction "3_3") (pintype "passive"))
    )
    (net (code "11") (name "/SEG_D") (class "Default")
      (node (ref "LED_D1") (pin "A") (pinfunction "A_A") (pintype "passive"))
      (node (ref "LED_D10") (pin "A") (pinfunction "A_A") (pintype "passive"))
      (node (ref "LED_D11") (pin "A") (pinfunction "A_A") (pintype "passive"))
      (node (ref "LED_D12") (pin "A") (pinfunction "A_A") (pintype "passive"))
      (node (ref "LED_D2") (pin "A") (pinfunction "A_A") (pintype "passive"))
      (node (ref "LED_D3") (pin "A") (pinfunction "A_A") (pintype "passive"))
      (node (ref "LED_D4") (pin "A") (pinfunction "A_A") (pintype "passive"))
      (node (ref "LED_D9") (pin "A") (pinfunction "A_A") (pintype "passive"))
      (node (ref "SV1") (pin "4") (pinfunction "4_4") (pintype "passive"))
      (node (ref "SV5") (pin "4") (pinfunction "4_4") (pintype "passive"))
    )
    (net (code "12") (name "/SEG_E") (class "Default")
      (node (ref "LED_E1") (pin "A") (pinfunction "A_A") (pintype "passive"))
      (node (ref "LED_E10") (pin "A") (pinfunction "A_A") (pintype "passive"))
      (node (ref "LED_E11") (pin "A") (pinfunction "A_A") (pintype "passive"))
      (node (ref "LED_E12") (pin "A") (pinfunction "A_A") (pintype "passive"))
      (node (ref "LED_E2") (pin "A") (pinfunction "A_A") (pintype "passive"))
      (node (ref "LED_E3") (pin "A") (pinfunction "A_A") (pintype "passive"))
      (node (ref "LED_E4") (pin "A") (pinfunction "A_A") (pintype "passive"))
      (node (ref "LED_E9") (pin "A") (pinfunction "A_A") (pintype "passive"))
      (node (ref "SV1") (pin "5") (pinfunction "5_5") (pintype "passive"))
      (node (ref "SV5") (pin "5") (pinfunction "5_5") (pintype "passive"))
    )
    (net (code "13") (name "/SEG_F") (class "Default")
      (node (ref "LED_F1") (pin "A") (pinfunction "A_A") (pintype "passive"))
      (node (ref "LED_F10") (pin "A") (pinfunction "A_A") (pintype "passive"))
      (node (ref "LED_F11") (pin "A") (pinfunction "A_A") (pintype "passive"))
      (node (ref "LED_F12") (pin "A") (pinfunction "A_A") (pintype "passive"))
      (node (ref "LED_F2") (pin "A") (pinfunction "A_A") (pintype "passive"))
      (node (ref "LED_F3") (pin "A") (pinfunction "A_A") (pintype "passive"))
      (node (ref "LED_F4") (pin "A") (pinfunction "A_A") (pintype "passive"))
      (node (ref "LED_F9") (pin "A") (pinfunction "A_A") (pintype "passive"))
      (node (ref "SV1") (pin "6") (pinfunction "6_6") (pintype "passive"))
      (node (ref "SV5") (pin "6") (pinfunction "6_6") (pintype "passive"))
    )
    (net (code "14") (name "/SEG_G") (class "Default")
      (node (ref "LED_G1") (pin "A") (pinfunction "A_A") (pintype "passive"))
      (node (ref "LED_G10") (pin "A") (pinfunction "A_A") (pintype "passive"))
      (node (ref "LED_G11") (pin "A") (pinfunction "A_A") (pintype "passive"))
      (node (ref "LED_G12") (pin "A") (pinfunction "A_A") (pintype "passive"))
      (node (ref "LED_G2") (pin "A") (pinfunction "A_A") (pintype "passive"))
      (node (ref "LED_G3") (pin "A") (pinfunction "A_A") (pintype "passive"))
      (node (ref "LED_G4") (pin "A") (pinfunction "A_A") (pintype "passive"))
      (node (ref "LED_G9") (pin "A") (pinfunction "A_A") (pintype "passive"))
      (node (ref "SV1") (pin "7") (pinfunction "7_7") (pintype "passive"))
      (node (ref "SV5") (pin "7") (pinfunction "7_7") (pintype "passive"))
    )
    (net (code "15") (name "/SEG_H") (class "Default")
      (node (ref "LED_H1") (pin "A") (pinfunction "A_A") (pintype "passive"))
      (node (ref "LED_H10") (pin "A") (pinfunction "A_A") (pintype "passive"))
      (node (ref "LED_H11") (pin "A") (pinfunction "A_A") (pintype "passive"))
      (node (ref "LED_H12") (pin "A") (pinfunction "A_A") (pintype "passive"))
      (node (ref "LED_H2") (pin "A") (pinfunction "A_A") (pintype "passive"))
      (node (ref "LED_H3") (pin "A") (pinfunction "A_A") (pintype "passive"))
      (node (ref "LED_H4") (pin "A") (pinfunction "A_A") (pintype "passive"))
      (node (ref "LED_H9") (pin "A") (pinfunction "A_A") (pintype "passive"))
      (node (ref "SV1") (pin "8") (pinfunction "8_8") (pintype "passive"))
      (node (ref "SV5") (pin "8") (pinfunction "8_8") (pintype "passive"))
    )
    (net (code "16") (name "/SEG_K") (class "Default")
      (node (ref "LED_K1") (pin "A") (pinfunction "A_A") (pintype "passive"))
      (node (ref "LED_K10") (pin "A") (pinfunction "A_A") (pintype "passive"))
      (node (ref "LED_K11") (pin "A") (pinfunction "A_A") (pintype "passive"))
      (node (ref "LED_K12") (pin "A") (pinfunction "A_A") (pintype "passive"))
      (node (ref "LED_K2") (pin "A") (pinfunction "A_A") (pintype "passive"))
      (node (ref "LED_K3") (pin "A") (pinfunction "A_A") (pintype "passive"))
      (node (ref "LED_K4") (pin "A") (pinfunction "A_A") (pintype "passive"))
      (node (ref "LED_K9") (pin "A") (pinfunction "A_A") (pintype "passive"))
      (node (ref "SV1") (pin "9") (pinfunction "9_9") (pintype "passive"))
      (node (ref "SV5") (pin "9") (pinfunction "9_9") (pintype "passive"))
    )
    (net (code "17") (name "/SEG_M") (class "Default")
      (node (ref "LED_M1") (pin "A") (pinfunction "A_A") (pintype "passive"))
      (node (ref "LED_M10") (pin "A") (pinfunction "A_A") (pintype "passive"))
      (node (ref "LED_M11") (pin "A") (pinfunction "A_A") (pintype "passive"))
      (node (ref "LED_M12") (pin "A") (pinfunction "A_A") (pintype "passive"))
      (node (ref "LED_M2") (pin "A") (pinfunction "A_A") (pintype "passive"))
      (node (ref "LED_M3") (pin "A") (pinfunction "A_A") (pintype "passive"))
      (node (ref "LED_M4") (pin "A") (pinfunction "A_A") (pintype "passive"))
      (node (ref "LED_M9") (pin "A") (pinfunction "A_A") (pintype "passive"))
      (node (ref "SV1") (pin "10") (pinfunction "10_10") (pintype "passive"))
      (node (ref "SV5") (pin "10") (pinfunction "10_10") (pintype "passive"))
    )
    (net (code "18") (name "/SEG_N") (class "Default")
      (node (ref "LED_N1") (pin "A") (pinfunction "A_A") (pintype "passive"))
      (node (ref "LED_N10") (pin "A") (pinfunction "A_A") (pintype "passive"))
      (node (ref "LED_N11") (pin "A") (pinfunction "A_A") (pintype "passive"))
      (node (ref "LED_N12") (pin "A") (pinfunction "A_A") (pintype "passive"))
      (node (ref "LED_N2") (pin "A") (pinfunction "A_A") (pintype "passive"))
      (node (ref "LED_N3") (pin "A") (pinfunction "A_A") (pintype "passive"))
      (node (ref "LED_N4") (pin "A") (pinfunction "A_A") (pintype "passive"))
      (node (ref "LED_N9") (pin "A") (pinfunction "A_A") (pintype "passive"))
      (node (ref "SV2") (pin "1") (pinfunction "1_1") (pintype "passive"))
      (node (ref "SV6") (pin "1") (pinfunction "1_1") (pintype "passive"))
    )
    (net (code "19") (name "/SEG_P") (class "Default")
      (node (ref "LED_P1") (pin "A") (pinfunction "A_A") (pintype "passive"))
      (node (ref "LED_P10") (pin "A") (pinfunction "A_A") (pintype "passive"))
      (node (ref "LED_P11") (pin "A") (pinfunction "A_A") (pintype "passive"))
      (node (ref "LED_P12") (pin "A") (pinfunction "A_A") (pintype "passive"))
      (node (ref "LED_P2") (pin "A") (pinfunction "A_A") (pintype "passive"))
      (node (ref "LED_P3") (pin "A") (pinfunction "A_A") (pintype "passive"))
      (node (ref "LED_P4") (pin "A") (pinfunction "A_A") (pintype "passive"))
      (node (ref "LED_P9") (pin "A") (pinfunction "A_A") (pintype "passive"))
      (node (ref "SV2") (pin "2") (pinfunction "2_2") (pintype "passive"))
      (node (ref "SV6") (pin "2") (pinfunction "2_2") (pintype "passive"))
    )
    (net (code "20") (name "/SEG_R") (class "Default")
      (node (ref "LED_R1") (pin "A") (pinfunction "A_A") (pintype "passive"))
      (node (ref "LED_R10") (pin "A") (pinfunction "A_A") (pintype "passive"))
      (node (ref "LED_R11") (pin "A") (pinfunction "A_A") (pintype "passive"))
      (node (ref "LED_R12") (pin "A") (pinfunction "A_A") (pintype "passive"))
      (node (ref "LED_R2") (pin "A") (pinfunction "A_A") (pintype "passive"))
      (node (ref "LED_R3") (pin "A") (pinfunction "A_A") (pintype "passive"))
      (node (ref "LED_R4") (pin "A") (pinfunction "A_A") (pintype "passive"))
      (node (ref "LED_R9") (pin "A") (pinfunction "A_A") (pintype "passive"))
      (node (ref "SV2") (pin "3") (pinfunction "3_3") (pintype "passive"))
      (node (ref "SV6") (pin "3") (pinfunction "3_3") (pintype "passive"))
    )
    (net (code "21") (name "/SEG_S") (class "Default")
      (node (ref "LED_S1") (pin "A") (pinfunction "A_A") (pintype "passive"))
      (node (ref "LED_S10") (pin "A") (pinfunction "A_A") (pintype "passive"))
      (node (ref "LED_S11") (pin "A") (pinfunction "A_A") (pintype "passive"))
      (node (ref "LED_S12") (pin "A") (pinfunction "A_A") (pintype "passive"))
      (node (ref "LED_S2") (pin "A") (pinfunction "A_A") (pintype "passive"))
      (node (ref "LED_S3") (pin "A") (pinfunction "A_A") (pintype "passive"))
      (node (ref "LED_S4") (pin "A") (pinfunction "A_A") (pintype "passive"))
      (node (ref "LED_S9") (pin "A") (pinfunction "A_A") (pintype "passive"))
      (node (ref "SV2") (pin "4") (pinfunction "4_4") (pintype "passive"))
      (node (ref "SV6") (pin "4") (pinfunction "4_4") (pintype "passive"))
    )
    (net (code "22") (name "/SEG_T") (class "Default")
      (node (ref "LED_T1") (pin "A") (pinfunction "A_A") (pintype "passive"))
      (node (ref "LED_T10") (pin "A") (pinfunction "A_A") (pintype "passive"))
      (node (ref "LED_T11") (pin "A") (pinfunction "A_A") (pintype "passive"))
      (node (ref "LED_T12") (pin "A") (pinfunction "A_A") (pintype "passive"))
      (node (ref "LED_T2") (pin "A") (pinfunction "A_A") (pintype "passive"))
      (node (ref "LED_T3") (pin "A") (pinfunction "A_A") (pintype "passive"))
      (node (ref "LED_T4") (pin "A") (pinfunction "A_A") (pintype "passive"))
      (node (ref "LED_T9") (pin "A") (pinfunction "A_A") (pintype "passive"))
      (node (ref "SV2") (pin "5") (pinfunction "5_5") (pintype "passive"))
      (node (ref "SV6") (pin "5") (pinfunction "5_5") (pintype "passive"))
    )
    (net (code "23") (name "/SEG_U") (class "Default")
      (node (ref "LED_U1") (pin "A") (pinfunction "A_A") (pintype "passive"))
      (node (ref "LED_U10") (pin "A") (pinfunction "A_A") (pintype "passive"))
      (node (ref "LED_U11") (pin "A") (pinfunction "A_A") (pintype "passive"))
      (node (ref "LED_U12") (pin "A") (pinfunction "A_A") (pintype "passive"))
      (node (ref "LED_U2") (pin "A") (pinfunction "A_A") (pintype "passive"))
      (node (ref "LED_U3") (pin "A") (pinfunction "A_A") (pintype "passive"))
      (node (ref "LED_U4") (pin "A") (pinfunction "A_A") (pintype "passive"))
      (node (ref "LED_U9") (pin "A") (pinfunction "A_A") (pintype "passive"))
      (node (ref "SV2") (pin "6") (pinfunction "6_6") (pintype "passive"))
      (node (ref "SV6") (pin "6") (pinfunction "6_6") (pintype "passive"))
    )
    (net (code "24") (name "unconnected-(SV1-Pad11)") (class "Default")
      (node (ref "SV1") (pin "11") (pinfunction "11_11") (pintype "passive"))
    )
    (net (code "25") (name "unconnected-(SV5-Pad11)") (class "Default")
      (node (ref "SV5") (pin "11") (pinfunction "11_11") (pintype "passive"))
    )
  )
)
